# AlarmTimer_Schematic.net
KiCad netlist of a schematic drawn in Altium Designer
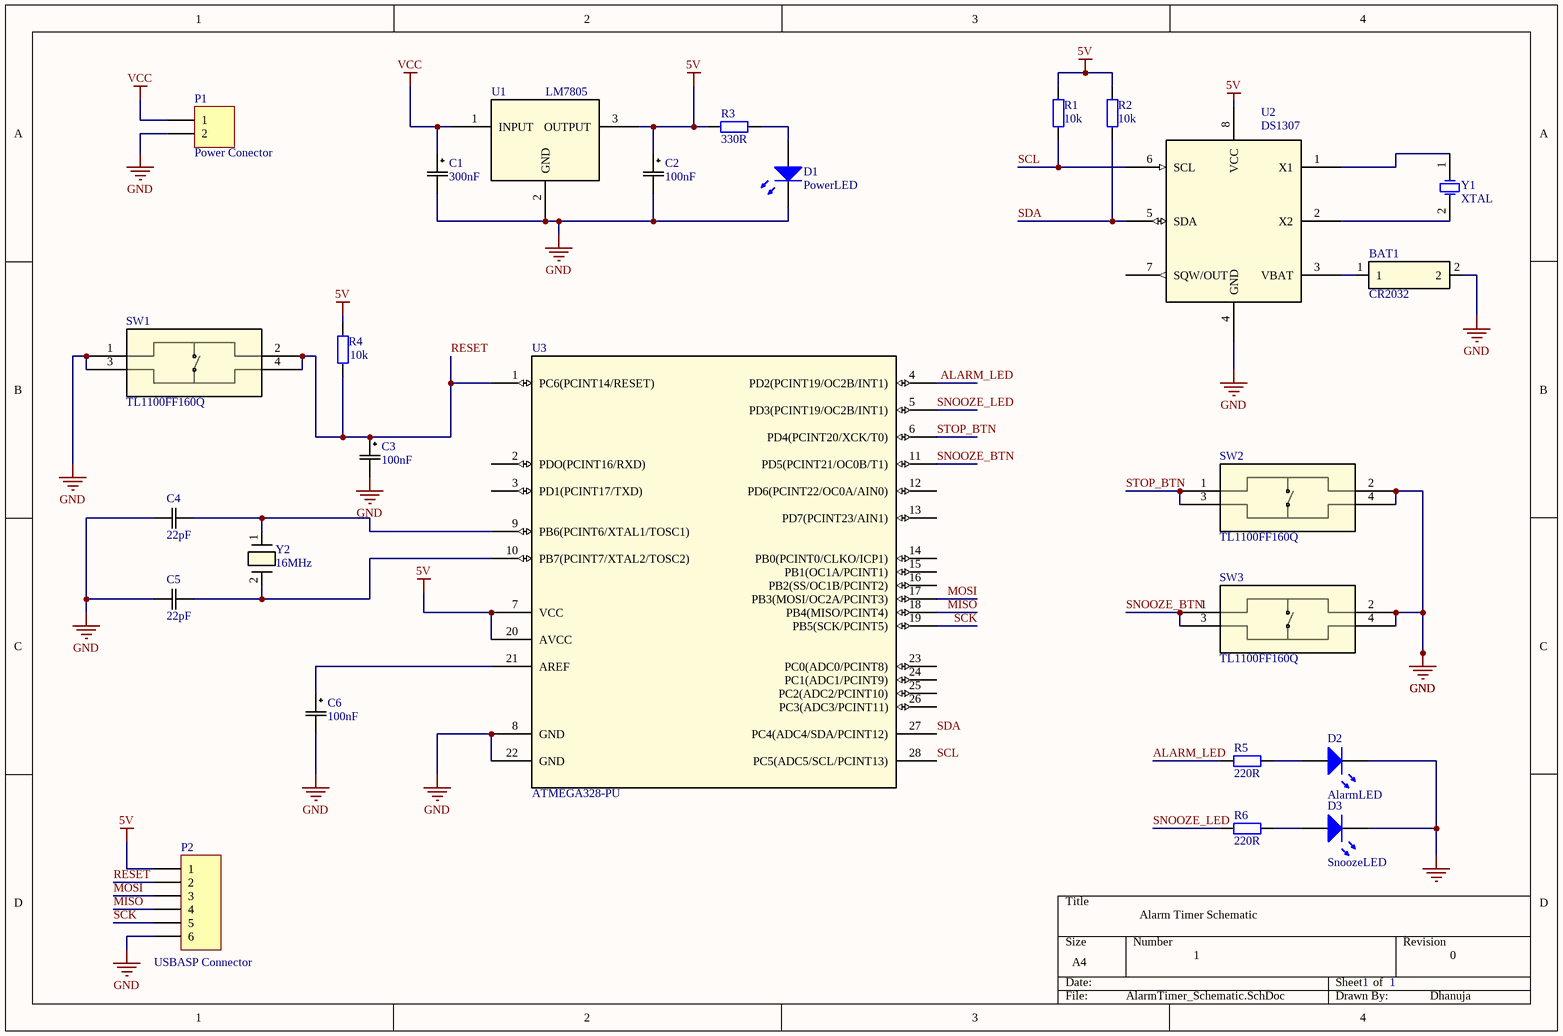
[diagram p0: AlarmTimer_Schematic.SchDoc]

(export (version "E")
  (design (tool "Eeschema 10.0.6"))
  (components
    (comp (ref "BAT1")
      (value "CR2032")
      (footprint "BAT_SMTU2032_RNB")
      (description "No Description Available")
      (fields
        (field (name "MANUFACTURER_PART_NUMBER") "SMTU2032")
        (field (name "COPYRIGHT") "Copyright (C) 2018 Accelerated Designs. All rights reserved")
      )
      (libsource (lib "CR2032_LiCell") (part "SMTU2032"))
    )
    (comp (ref "C1")
      (value "300nF")
      (footprint "CAP_UEP_5X11_NCH")
      (description "No Description Available")
      (fields
        (field (name "MANUFACTURER_PART_NUMBER") "UFW2A0R1MDD1TD")
        (field (name "COPYRIGHT") "Copyright (C) 2018 Accelerated Designs. All rights reserved")
      )
      (libsource (lib "Polarized Capacitor") (part "Cap Pol"))
    )
    (comp (ref "C2")
      (value "100nF")
      (footprint "CAP_UEP_5X11_NCH")
      (description "No Description Available")
      (fields
        (field (name "MANUFACTURER_PART_NUMBER") "UFW2A0R1MDD1TD")
        (field (name "COPYRIGHT") "Copyright (C) 2018 Accelerated Designs. All rights reserved")
      )
      (libsource (lib "Polarized Capacitor") (part "Cap Pol"))
    )
    (comp (ref "C3")
      (value "100nF")
      (footprint "CAP_UEP_5X11_NCH")
      (description "No Description Available")
      (fields
        (field (name "MANUFACTURER_PART_NUMBER") "UFW2A0R1MDD1TD")
        (field (name "COPYRIGHT") "Copyright (C) 2018 Accelerated Designs. All rights reserved")
      )
      (libsource (lib "Polarized Capacitor") (part "Cap Pol"))
    )
    (comp (ref "C4")
      (value "22pF")
      (footprint "CAP_FA28_TDK")
      (description "No Description Available")
      (fields
        (field (name "MANUFACTURER_PART_NUMBER") "FA28C0G1H220JNU00")
        (field (name "COPYRIGHT") "Copyright (C) 2018 Accelerated Designs. All rights reserved")
      )
      (libsource (lib "22pF Capacitor") (part "FA28C0G1H220JNU00"))
    )
    (comp (ref "C5")
      (value "22pF")
      (footprint "CAP_FA28_TDK")
      (description "No Description Available")
      (fields
        (field (name "MANUFACTURER_PART_NUMBER") "FA28C0G1H220JNU00")
        (field (name "COPYRIGHT") "Copyright (C) 2018 Accelerated Designs. All rights reserved")
      )
      (libsource (lib "22pF Capacitor") (part "FA28C0G1H220JNU00"))
    )
    (comp (ref "C6")
      (value "100nF")
      (footprint "CAP_UEP_5X11_NCH")
      (description "No Description Available")
      (fields
        (field (name "MANUFACTURER_PART_NUMBER") "UFW2A0R1MDD1TD")
        (field (name "COPYRIGHT") "Copyright (C) 2018 Accelerated Designs. All rights reserved")
      )
      (libsource (lib "Polarized Capacitor") (part "Cap Pol"))
    )
    (comp (ref "D1") (value "PowerLED") (footprint "LED") (libsource (lib "LED") (part "LED")))
    (comp (ref "D2") (value "AlarmLED") (footprint "LED") (libsource (lib "LED") (part "LED")))
    (comp (ref "D3") (value "SnoozeLED") (footprint "LED") (libsource (lib "LED") (part "LED")))
    (comp (ref "P1")
      (value "Power Conector")
      (footprint "HDR1X2H")
      (description "Header, 2-Pin, Right Angle")
      (fields (field (name "PUBLISHER") "Altium Limited"))
      (libsource (lib "Miscellaneous Connectors") (part "Header 2H"))
    )
    (comp (ref "P2")
      (value "USBASP Connector")
      (footprint "HDR1X6H")
      (description "Header, 6-Pin, Right Angle")
      (fields (field (name "PUBLISHER") "Altium Limited"))
      (libsource (lib "Miscellaneous Connectors") (part "Header 6H"))
    )
    (comp (ref "R1")
      (value "10k")
      (footprint "AXIAL-0.4")
      (description "Resistor")
      (fields (field (name "PUBLISHER") "Altium Limited"))
      (libsource (lib "Miscellaneous Devices") (part "Res2"))
    )
    (comp (ref "R2")
      (value "10k")
      (footprint "AXIAL-0.4")
      (description "Resistor")
      (fields (field (name "PUBLISHER") "Altium Limited"))
      (libsource (lib "Miscellaneous Devices") (part "Res2"))
    )
    (comp (ref "R3")
      (value "330R")
      (footprint "AXIAL-0.4")
      (description "Resistor")
      (fields (field (name "PUBLISHER") "Altium Limited"))
      (libsource (lib "") (part "Res2_1"))
    )
    (comp (ref "R4")
      (value "10k")
      (footprint "AXIAL-0.4")
      (description "Resistor")
      (fields (field (name "PUBLISHER") "Altium Limited"))
      (libsource (lib "") (part "Res2_2"))
    )
    (comp (ref "R5")
      (value "220R")
      (footprint "AXIAL-0.4")
      (description "Resistor")
      (fields (field (name "PUBLISHER") "Altium Limited"))
      (libsource (lib "") (part "Res2_1"))
    )
    (comp (ref "R6")
      (value "220R")
      (footprint "AXIAL-0.4")
      (description "Resistor")
      (fields (field (name "PUBLISHER") "Altium Limited"))
      (libsource (lib "") (part "Res2_1"))
    )
    (comp (ref "SW1")
      (value "TL1100FF160Q")
      (footprint "TL1100F")
      (description "No Description Available")
      (fields (field (name "COPYRIGHT") "Copyright (C) 2018 Accelerated Designs. All rights reserved"))
      (libsource (lib "TL1100 Tactile Switch") (part "TL1100FF160Q"))
    )
    (comp (ref "SW2")
      (value "TL1100FF160Q")
      (footprint "TL1100F")
      (description "No Description Available")
      (fields (field (name "COPYRIGHT") "Copyright (C) 2018 Accelerated Designs. All rights reserved"))
      (libsource (lib "TL1100 Tactile Switch") (part "TL1100FF160Q"))
    )
    (comp (ref "SW3")
      (value "TL1100FF160Q")
      (footprint "TL1100F")
      (description "No Description Available")
      (fields (field (name "COPYRIGHT") "Copyright (C) 2018 Accelerated Designs. All rights reserved"))
      (libsource (lib "TL1100 Tactile Switch") (part "TL1100FF160Q"))
    )
    (comp (ref "U1")
      (value "LM7805")
      (footprint "TO-220_FAS")
      (description "No Description Available")
      (fields
        (field (name "MANUFACTURER_PART_NUMBER") "LM7805CT")
        (field (name "COPYRIGHT") "Copyright (C) 2018 Accelerated Designs. All rights reserved")
      )
      (libsource (lib "LM7805") (part "LM7805CT"))
    )
    (comp (ref "U2")
      (value "DS1307")
      (footprint "21-0043D_8_MXM")
      (description "No Description Available")
      (fields
        (field (name "MANUFACTURER_PART_NUMBER") "DS1307+")
        (field (name "COPYRIGHT") "Copyright (C) 2018 Accelerated Designs. All rights reserved")
      )
      (libsource (lib "DS1307") (part "DS1307+"))
    )
    (comp (ref "U3")
      (value "ATMEGA328-PU")
      (footprint "28P3_SPDIP28_SP_MCH")
      (description "No Description Available")
      (fields (field (name "COPYRIGHT") "Copyright (C) 2018 Accelerated Designs. All rights reserved"))
      (libsource (lib "ATmega328PU") (part "ATMEGA328-PU"))
    )
    (comp (ref "Y1")
      (value "XTAL")
      (footprint "R38")
      (description "Crystal Oscillator")
      (fields (field (name "PUBLISHER") "Altium Limited"))
      (libsource (lib "Miscellaneous Devices") (part "XTAL"))
    )
    (comp (ref "Y2")
      (value "16MHz")
      (footprint "XTAL_ABL_ABR")
      (description "No Description Available")
      (fields
        (field (name "MANUFACTURER_PART_NUMBER") "ABL-20.000MHZ-B2")
        (field (name "COPYRIGHT") "Copyright (C) 2018 Accelerated Designs. All rights reserved")
      )
      (libsource (lib "16MHz crystal") (part "16MHz"))
    )
  )
  (nets
    (net (code "1") (name "/ALARM_LED") (class "Default")
      (node (ref "R5") (pin "1") (pinfunction "1_1") (pintype "passive"))
      (node (ref "U3") (pin "4") (pinfunction "PD2(PCINT19/OC2B/INT1)_4") (pintype "bidirectional"))
    )
    (net (code "2") (name "/MISO") (class "Default")
      (node (ref "P2") (pin "4") (pinfunction "4_4") (pintype "passive"))
      (node (ref "U3") (pin "18") (pinfunction "PB4(MISO/PCINT4)_18") (pintype "bidirectional"))
    )
    (net (code "3") (name "/MOSI") (class "Default")
      (node (ref "P2") (pin "3") (pinfunction "3_3") (pintype "passive"))
      (node (ref "U3") (pin "17") (pinfunction "PB3(MOSI/OC2A/PCINT3)_17") (pintype "bidirectional"))
    )
    (net (code "4") (name "/RESET") (class "Default")
      (node (ref "C3") (pin "1") (pinfunction "1_1") (pintype "passive"))
      (node (ref "P2") (pin "2") (pinfunction "2_2") (pintype "passive"))
      (node (ref "R4") (pin "1") (pinfunction "1_1") (pintype "passive"))
      (node (ref "SW1") (pin "2") (pinfunction "2_2") (pintype "passive"))
      (node (ref "SW1") (pin "4") (pinfunction "4_4") (pintype "passive"))
      (node (ref "U3") (pin "1") (pinfunction "PC6(PCINT14/RESET)_1") (pintype "bidirectional"))
    )
    (net (code "5") (name "/SCK") (class "Default")
      (node (ref "P2") (pin "5") (pinfunction "5_5") (pintype "passive"))
      (node (ref "U3") (pin "19") (pinfunction "PB5(SCK/PCINT5)_19") (pintype "bidirectional"))
    )
    (net (code "6") (name "/SCL") (class "Default")
      (node (ref "R1") (pin "2") (pinfunction "2_2") (pintype "passive"))
      (node (ref "U2") (pin "6") (pinfunction "SCL_6") (pintype "input"))
      (node (ref "U3") (pin "28") (pinfunction "PC5(ADC5/SCL/PCINT13)_28") (pintype "open_collector"))
    )
    (net (code "7") (name "/SDA") (class "Default")
      (node (ref "R2") (pin "2") (pinfunction "2_2") (pintype "passive"))
      (node (ref "U2") (pin "5") (pinfunction "SDA_5") (pintype "bidirectional"))
      (node (ref "U3") (pin "27") (pinfunction "PC4(ADC4/SDA/PCINT12)_27") (pintype "open_collector"))
    )
    (net (code "8") (name "/SNOOZE_BTN") (class "Default")
      (node (ref "SW3") (pin "1") (pinfunction "1_1") (pintype "passive"))
      (node (ref "SW3") (pin "3") (pinfunction "3_3") (pintype "passive"))
      (node (ref "U3") (pin "11") (pinfunction "PD5(PCINT21/OC0B/T1)_11") (pintype "bidirectional"))
    )
    (net (code "9") (name "/SNOOZE_LED") (class "Default")
      (node (ref "R6") (pin "1") (pinfunction "1_1") (pintype "passive"))
      (node (ref "U3") (pin "5") (pinfunction "PD3(PCINT19/OC2B/INT1)_5") (pintype "bidirectional"))
    )
    (net (code "10") (name "/STOP_BTN") (class "Default")
      (node (ref "SW2") (pin "1") (pinfunction "1_1") (pintype "passive"))
      (node (ref "SW2") (pin "3") (pinfunction "3_3") (pintype "passive"))
      (node (ref "U3") (pin "6") (pinfunction "PD4(PCINT20/XCK/T0)_6") (pintype "bidirectional"))
    )
    (net (code "11") (name "5V") (class "Default")
      (node (ref "C2") (pin "1") (pinfunction "1_1") (pintype "passive"))
      (node (ref "P2") (pin "1") (pinfunction "1_1") (pintype "passive"))
      (node (ref "R1") (pin "1") (pinfunction "1_1") (pintype "passive"))
      (node (ref "R2") (pin "1") (pinfunction "1_1") (pintype "passive"))
      (node (ref "R3") (pin "1") (pinfunction "1_1") (pintype "passive"))
      (node (ref "R4") (pin "2") (pinfunction "2_2") (pintype "passive"))
      (node (ref "U1") (pin "3") (pinfunction "OUTPUT_3") (pintype "power_in"))
      (node (ref "U2") (pin "8") (pinfunction "VCC_8") (pintype "power_in"))
      (node (ref "U3") (pin "20") (pinfunction "AVCC_20") (pintype "power_in"))
      (node (ref "U3") (pin "7") (pinfunction "VCC_7") (pintype "power_in"))
    )
    (net (code "12") (name "GND") (class "Default")
      (node (ref "BAT1") (pin "2") (pinfunction "2_2") (pintype "passive"))
      (node (ref "C1") (pin "2") (pinfunction "2_2") (pintype "passive"))
      (node (ref "C2") (pin "2") (pinfunction "2_2") (pintype "passive"))
      (node (ref "C3") (pin "2") (pinfunction "2_2") (pintype "passive"))
      (node (ref "C4") (pin "1") (pinfunction "1_1") (pintype "passive"))
      (node (ref "C5") (pin "1") (pinfunction "1_1") (pintype "passive"))
      (node (ref "C6") (pin "2") (pinfunction "2_2") (pintype "passive"))
      (node (ref "D1") (pin "1") (pinfunction "1_1") (pintype "passive"))
      (node (ref "D2") (pin "1") (pinfunction "1_1") (pintype "passive"))
      (node (ref "D3") (pin "1") (pinfunction "1_1") (pintype "passive"))
      (node (ref "P1") (pin "2") (pinfunction "2_2") (pintype "passive"))
      (node (ref "P2") (pin "6") (pinfunction "6_6") (pintype "passive"))
      (node (ref "SW1") (pin "1") (pinfunction "1_1") (pintype "passive"))
      (node (ref "SW1") (pin "3") (pinfunction "3_3") (pintype "passive"))
      (node (ref "SW2") (pin "2") (pinfunction "2_2") (pintype "passive"))
      (node (ref "SW2") (pin "4") (pinfunction "4_4") (pintype "passive"))
      (node (ref "SW3") (pin "2") (pinfunction "2_2") (pintype "passive"))
      (node (ref "SW3") (pin "4") (pinfunction "4_4") (pintype "passive"))
      (node (ref "U1") (pin "2") (pinfunction "GND_2") (pintype "power_in"))
      (node (ref "U2") (pin "4") (pinfunction "GND_4") (pintype "power_in"))
      (node (ref "U3") (pin "22") (pinfunction "GND_22") (pintype "passive"))
      (node (ref "U3") (pin "8") (pinfunction "GND_8") (pintype "passive"))
    )
    (net (code "13") (name "Net-(D1-Pad2)") (class "Default")
      (node (ref "D1") (pin "2") (pinfunction "2_2") (pintype "passive"))
      (node (ref "R3") (pin "2") (pinfunction "2_2") (pintype "passive"))
    )
    (net (code "14") (name "Net-(D2-Pad2)") (class "Default")
      (node (ref "D2") (pin "2") (pinfunction "2_2") (pintype "passive"))
      (node (ref "R5") (pin "2") (pinfunction "2_2") (pintype "passive"))
    )
    (net (code "15") (name "Net-(D3-Pad2)") (class "Default")
      (node (ref "D3") (pin "2") (pinfunction "2_2") (pintype "passive"))
      (node (ref "R6") (pin "2") (pinfunction "2_2") (pintype "passive"))
    )
    (net (code "16") (name "Net-(U2-VBAT)") (class "Default")
      (node (ref "BAT1") (pin "1") (pinfunction "1_1") (pintype "passive"))
      (node (ref "U2") (pin "3") (pinfunction "VBAT_3") (pintype "power_in"))
    )
    (net (code "17") (name "Net-(U2-X1)") (class "Default")
      (node (ref "U2") (pin "1") (pinfunction "X1_1") (pintype "passive"))
      (node (ref "Y1") (pin "1") (pinfunction "OSC1_1") (pintype "passive"))
    )
    (net (code "18") (name "Net-(U2-X2)") (class "Default")
      (node (ref "U2") (pin "2") (pinfunction "X2_2") (pintype "passive"))
      (node (ref "Y1") (pin "2") (pinfunction "OSC2_2") (pintype "passive"))
    )
    (net (code "19") (name "Net-(U3-AREF)") (class "Default")
      (node (ref "C6") (pin "1") (pinfunction "1_1") (pintype "passive"))
      (node (ref "U3") (pin "21") (pinfunction "AREF_21") (pintype "passive"))
    )
    (net (code "20") (name "Net-(U3-PB6(PCINT6{slash}XTAL1{slash}TOSC1))") (class "Default")
      (node (ref "C4") (pin "2") (pinfunction "2_2") (pintype "passive"))
      (node (ref "U3") (pin "9") (pinfunction "PB6(PCINT6/XTAL1/TOSC1)_9") (pintype "bidirectional"))
      (node (ref "Y2") (pin "1") (pinfunction "1_1") (pintype "passive"))
    )
    (net (code "21") (name "Net-(U3-PB7(PCINT7{slash}XTAL2{slash}TOSC2))") (class "Default")
      (node (ref "C5") (pin "2") (pinfunction "2_2") (pintype "passive"))
      (node (ref "U3") (pin "10") (pinfunction "PB7(PCINT7/XTAL2/TOSC2)_10") (pintype "bidirectional"))
      (node (ref "Y2") (pin "2") (pinfunction "2_2") (pintype "passive"))
    )
    (net (code "22") (name "VCC") (class "Default")
      (node (ref "C1") (pin "1") (pinfunction "1_1") (pintype "passive"))
      (node (ref "P1") (pin "1") (pinfunction "1_1") (pintype "passive"))
      (node (ref "U1") (pin "1") (pinfunction "INPUT_1") (pintype "power_in"))
    )
    (net (code "23") (name "unconnected-(U2-SQW{slash}OUT-Pad7)") (class "Default")
      (node (ref "U2") (pin "7") (pinfunction "SQW/OUT_7") (pintype "output"))
    )
    (net (code "24") (name "unconnected-(U3-PB0(PCINT0{slash}CLKO{slash}ICP1)-Pad14)") (class "Default")
      (node (ref "U3") (pin "14") (pinfunction "PB0(PCINT0/CLKO/ICP1)_14") (pintype "bidirectional"))
    )
    (net (code "25") (name "unconnected-(U3-PB1(OC1A{slash}PCINT1)-Pad15)") (class "Default")
      (node (ref "U3") (pin "15") (pinfunction "PB1(OC1A/PCINT1)_15") (pintype "bidirectional"))
    )
    (net (code "26") (name "unconnected-(U3-PB2(SS{slash}OC1B{slash}PCINT2)-Pad16)") (class "Default")
      (node (ref "U3") (pin "16") (pinfunction "PB2(SS/OC1B/PCINT2)_16") (pintype "bidirectional"))
    )
    (net (code "27") (name "unconnected-(U3-PC0(ADC0{slash}PCINT8)-Pad23)") (class "Default")
      (node (ref "U3") (pin "23") (pinfunction "PC0(ADC0/PCINT8)_23") (pintype "bidirectional"))
    )
    (net (code "28") (name "unconnected-(U3-PC1(ADC1{slash}PCINT9)-Pad24)") (class "Default")
      (node (ref "U3") (pin "24") (pinfunction "PC1(ADC1/PCINT9)_24") (pintype "bidirectional"))
    )
    (net (code "29") (name "unconnected-(U3-PC2(ADC2{slash}PCINT10)-Pad25)") (class "Default")
      (node (ref "U3") (pin "25") (pinfunction "PC2(ADC2/PCINT10)_25") (pintype "bidirectional"))
    )
    (net (code "30") (name "unconnected-(U3-PC3(ADC3{slash}PCINT11)-Pad26)") (class "Default")
      (node (ref "U3") (pin "26") (pinfunction "PC3(ADC3/PCINT11)_26") (pintype "bidirectional"))
    )
    (net (code "31") (name "unconnected-(U3-PD1(PCINT17{slash}TXD)-Pad3)") (class "Default")
      (node (ref "U3") (pin "3") (pinfunction "PD1(PCINT17/TXD)_3") (pintype "bidirectional"))
    )
    (net (code "32") (name "unconnected-(U3-PD6(PCINT22{slash}OC0A{slash}AIN0)-Pad12)") (class "Default")
      (node (ref "U3") (pin "12") (pinfunction "PD6(PCINT22/OC0A/AIN0)_12") (pintype "bidirectional"))
    )
    (net (code "33") (name "unconnected-(U3-PD7(PCINT23{slash}AIN1)-Pad13)") (class "Default")
      (node (ref "U3") (pin "13") (pinfunction "PD7(PCINT23/AIN1)_13") (pintype "bidirectional"))
    )
    (net (code "34") (name "unconnected-(U3-PDO(PCINT16{slash}RXD)-Pad2)") (class "Default")
      (node (ref "U3") (pin "2") (pinfunction "PDO(PCINT16/RXD)_2") (pintype "bidirectional"))
    )
  )
)
